# SampleLDO_Schematic.net
KiCad netlist of a schematic drawn in Altium Designer
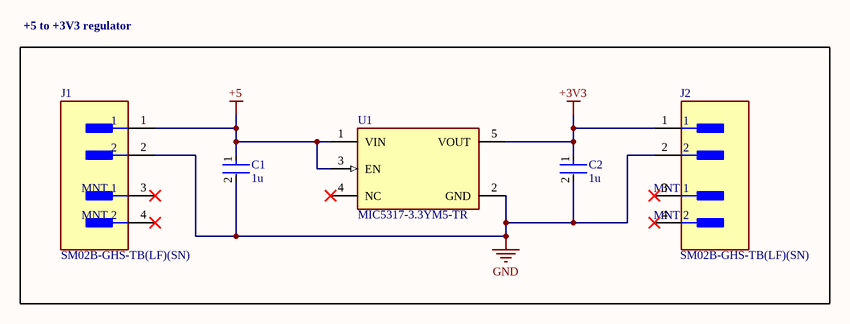
[diagram p0: SampleLDO_Schematic.SchDoc]

(export (version "E")
  (design (tool "Eeschema 10.0.6"))
  (components
    (comp (ref "C1")
      (value "1u")
      (footprint "FP-CC0805-0_85-MFG")
      (description "CAP CER 1UF 10V X7R 0805")
      (fields
        (field (name "MANUFACTURER") "Yageo")
        (field (name "OCTOPART") "https://octopart.com/cc0805kkx7r6bb105-yageo-42522859")
      )
      (libsource (lib "Altium Content Vault") (part "11868f565c42a9108669ba33697ecf6"))
    )
    (comp (ref "C2")
      (value "1u")
      (footprint "FP-CC0805-0_85-MFG")
      (description "CAP CER 1UF 10V X7R 0805")
      (fields
        (field (name "MANUFACTURER") "Yageo")
        (field (name "OCTOPART") "https://octopart.com/cc0805kkx7r6bb105-yageo-42522859")
      )
      (libsource (lib "Altium Content Vault") (part "11868f565c42a9108669ba33697ecf6"))
    )
    (comp (ref "J1")
      (value "SM02B-GHS-TB(LF)(SN)")
      (footprint "FP-SM02B-GHS-TB_LF_SN-MFG")
      (description "CONN HEADER SMD R/A 2POS 1.25MM")
      (libsource (lib "") (part "56ec3178a87b3978bdc1b3682cd516a_1"))
    )
    (comp (ref "J2")
      (value "SM02B-GHS-TB(LF)(SN)")
      (footprint "FP-SM02B-GHS-TB_LF_SN-MFG")
      (description "CONN HEADER SMD R/A 2POS 1.25MM")
      (libsource (lib "Altium Content Vault") (part "56ec3178a87b3978bdc1b3682cd516a"))
    )
    (comp (ref "U1")
      (value "MIC5317-3.3YM5-TR")
      (footprint "FP-SOT23-5LD-PL-1-MFG")
      (description "IC REG LINEAR 3.3V 150MA SOT23-5")
      (libsource (lib "Altium Content Vault") (part "0a093dae7315cdc977fd108dde87457"))
    )
  )
  (nets
    (net (code "1") (name "+3V3") (class "Default")
      (node (ref "C2") (pin "1") (pinfunction "1_1") (pintype "passive"))
      (node (ref "J2") (pin "1") (pinfunction "1_1") (pintype "passive"))
      (node (ref "U1") (pin "5") (pinfunction "VOUT_5") (pintype "power_in"))
    )
    (net (code "2") (name "+5") (class "Default")
      (node (ref "C1") (pin "1") (pinfunction "1_1") (pintype "passive"))
      (node (ref "J1") (pin "1") (pinfunction "1_1") (pintype "passive"))
      (node (ref "U1") (pin "1") (pinfunction "VIN_1") (pintype "power_in"))
      (node (ref "U1") (pin "3") (pinfunction "EN_3") (pintype "input"))
    )
    (net (code "3") (name "GND") (class "Default")
      (node (ref "C1") (pin "2") (pinfunction "2_2") (pintype "passive"))
      (node (ref "C2") (pin "2") (pinfunction "2_2") (pintype "passive"))
      (node (ref "J1") (pin "2") (pinfunction "2_2") (pintype "passive"))
      (node (ref "J2") (pin "2") (pinfunction "2_2") (pintype "passive"))
      (node (ref "U1") (pin "2") (pinfunction "GND_2") (pintype "power_in"))
    )
    (net (code "4") (name "unconnected-(J1-MNT_1-Pad3)") (class "Default")
      (node (ref "J1") (pin "3") (pinfunction "MNT_1_3") (pintype "passive+no_connect"))
    )
    (net (code "5") (name "unconnected-(J1-MNT_2-Pad4)") (class "Default")
      (node (ref "J1") (pin "4") (pinfunction "MNT_2_4") (pintype "passive+no_connect"))
    )
    (net (code "6") (name "unconnected-(J2-MNT_1-Pad3)") (class "Default")
      (node (ref "J2") (pin "3") (pinfunction "MNT_1_3") (pintype "passive+no_connect"))
    )
    (net (code "7") (name "unconnected-(J2-MNT_2-Pad4)") (class "Default")
      (node (ref "J2") (pin "4") (pinfunction "MNT_2_4") (pintype "passive+no_connect"))
    )
    (net (code "8") (name "unconnected-(U1-NC-Pad4)") (class "Default")
      (node (ref "U1") (pin "4") (pinfunction "NC_4") (pintype "passive+no_connect"))
    )
  )
)
